# Grove_-_2_Channel_Inductive_Sensor_LDC16.net
KiCad netlist of a schematic drawn in EAGLE
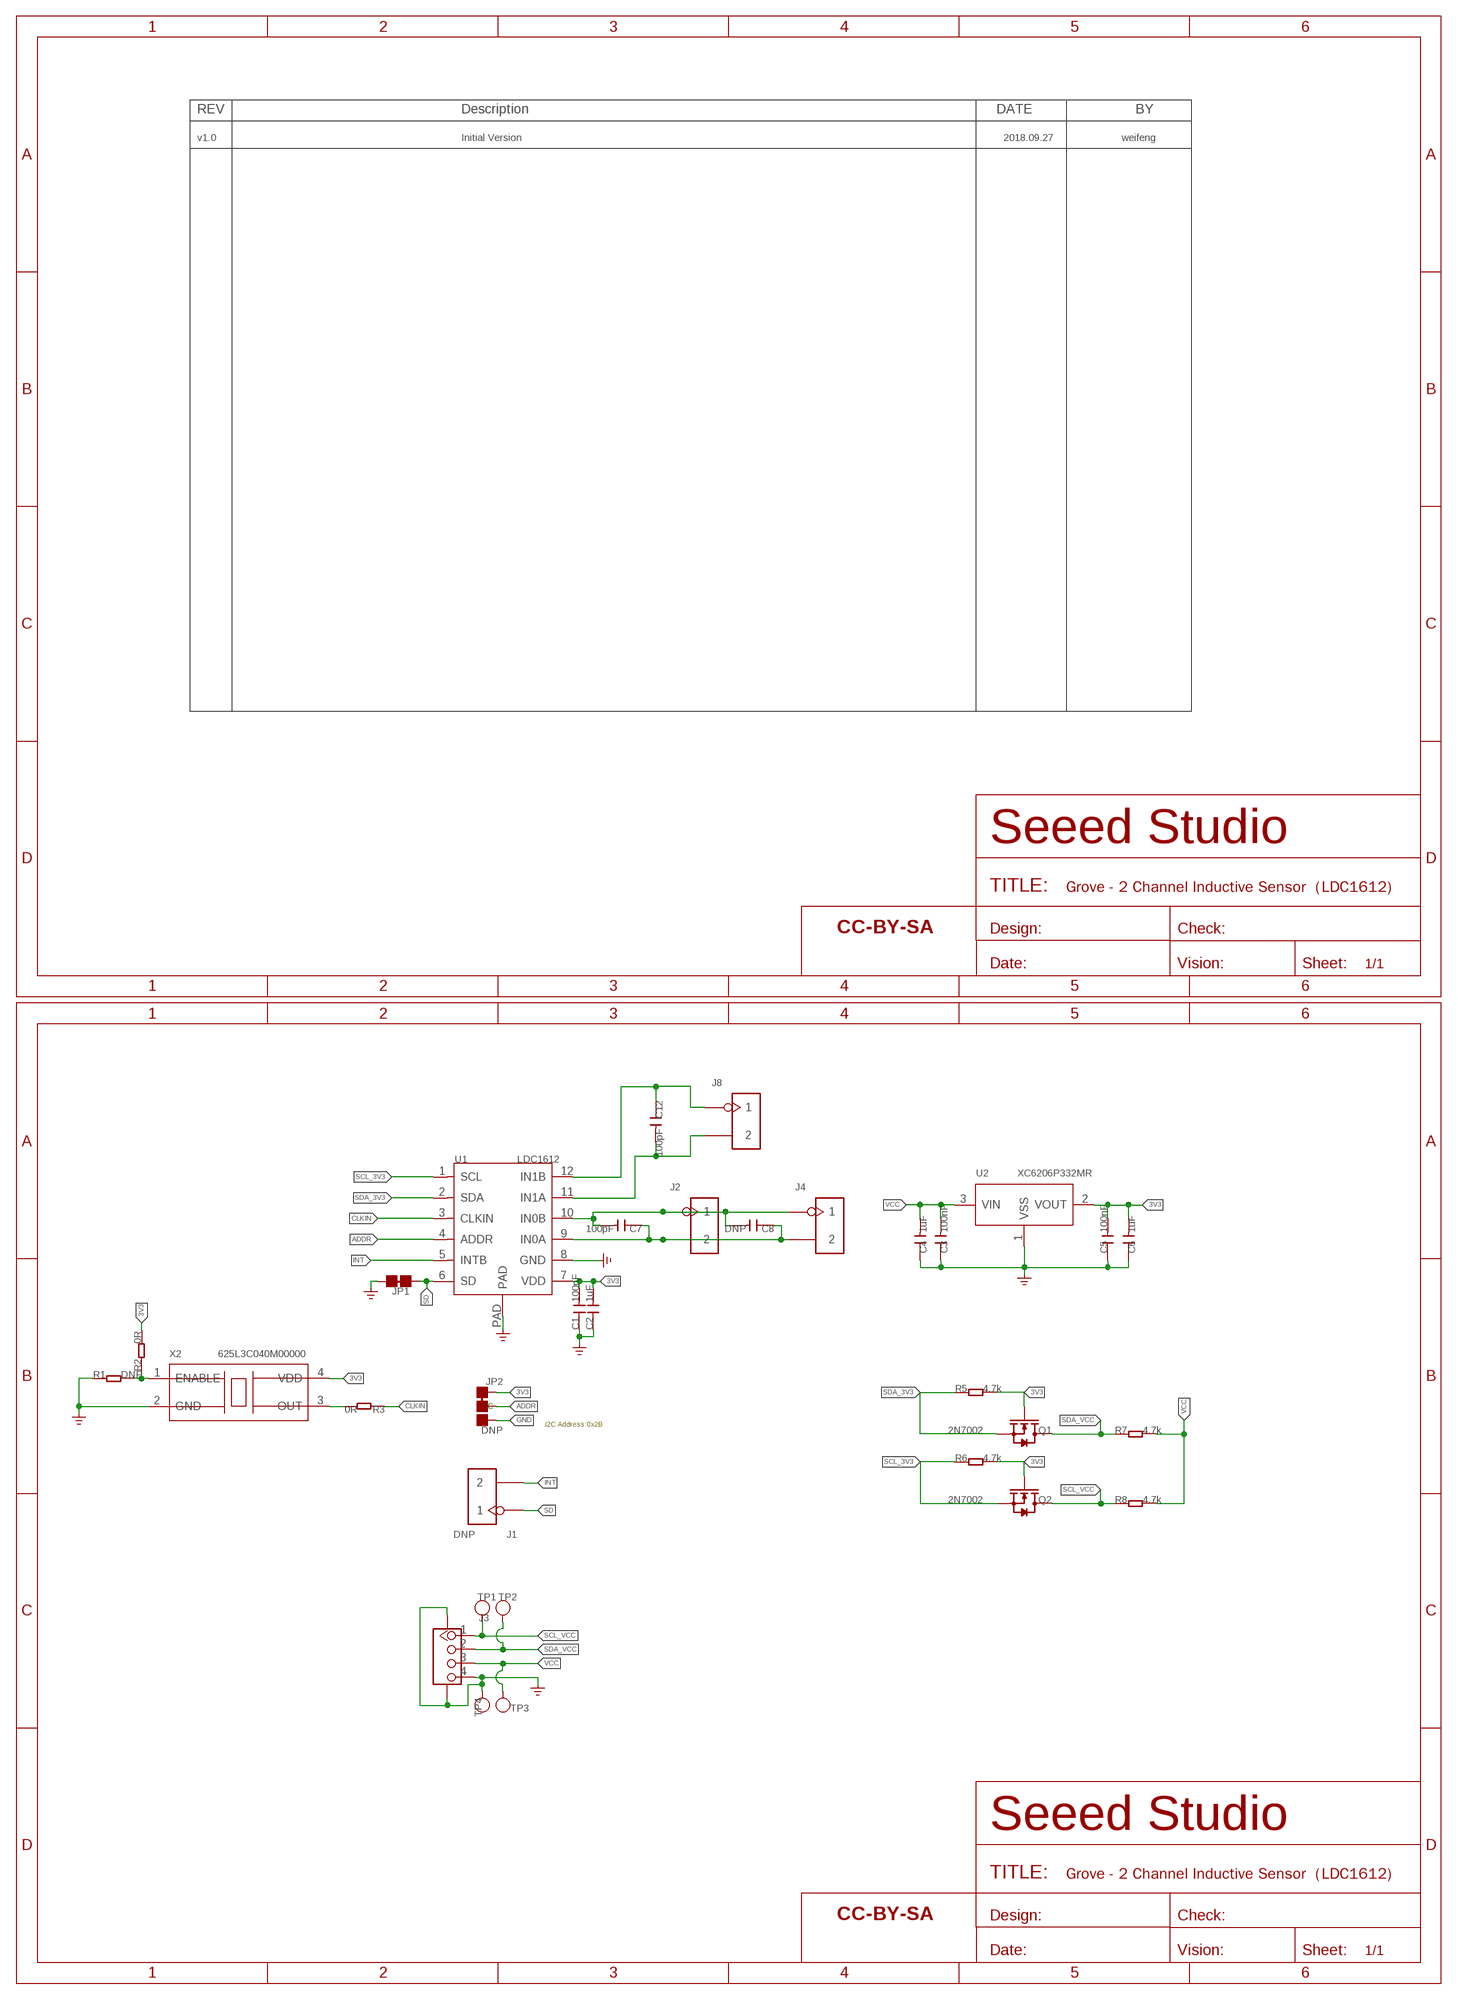
[diagram p0: schematic, sheet 1]

(export (version "E")
  (design (tool "Eeschema 10.0.6"))
  (components
    (comp (ref "C1")
      (value "100nF")
      (footprint "eagle-import:C0603")
      (libsource (lib "eagle-import") (part "CAP-0603"))
    )
    (comp (ref "C2")
      (value "1uF")
      (footprint "eagle-import:C0603")
      (libsource (lib "eagle-import") (part "CAP-0603"))
    )
    (comp (ref "C3")
      (value "100nF")
      (footprint "eagle-import:C0603")
      (libsource (lib "eagle-import") (part "CAP-0603"))
    )
    (comp (ref "C4")
      (value "1uF")
      (footprint "eagle-import:C0603")
      (libsource (lib "eagle-import") (part "CAP-0603"))
    )
    (comp (ref "C5")
      (value "100nF")
      (footprint "eagle-import:C0603")
      (libsource (lib "eagle-import") (part "CAP-0603"))
    )
    (comp (ref "C6")
      (value "1uF")
      (footprint "eagle-import:C0603")
      (libsource (lib "eagle-import") (part "CAP-0603"))
    )
    (comp (ref "C7")
      (value "100pF")
      (footprint "eagle-import:C0603")
      (libsource (lib "eagle-import") (part "CAP-0603"))
    )
    (comp (ref "C8")
      (value "DNP")
      (footprint "eagle-import:C0603")
      (libsource (lib "eagle-import") (part "CAP-0603"))
    )
    (comp (ref "C12")
      (value "100pF")
      (footprint "eagle-import:C0603")
      (libsource (lib "eagle-import") (part "CAP-0603"))
    )
    (comp (ref "FR1")
      (value "SEEEDSTUDIO-OPEN-SCH-FRAME")
      (footprint "eagle-import:SEEEDSTUDIO-PCB-FRAME")
      (libsource (lib "eagle-import") (part "SEEEDSTUDIO-OPEN-SCH-FRAME"))
    )
    (comp (ref "J1")
      (value "DNP")
      (footprint "eagle-import:H2-2.54")
      (libsource (lib "eagle-import") (part "HEADER-2P-65/35MIL"))
    )
    (comp (ref "J2")
      (value "HEADER-2P-65/35MIL")
      (footprint "eagle-import:H2-2.54")
      (libsource (lib "eagle-import") (part "HEADER-2P-65/35MIL"))
    )
    (comp (ref "J3")
      (value "GROVE-CONNECTOR-SMD'DD'")
      (footprint "eagle-import:HW4-SMD-2.0")
      (libsource (lib "eagle-import") (part "GROVE-CONNECTOR-SMD'DD'"))
    )
    (comp (ref "J4")
      (value "HEADER-2P-65/35MIL")
      (footprint "eagle-import:H2-2.54")
      (libsource (lib "eagle-import") (part "HEADER-2P-65/35MIL"))
    )
    (comp (ref "J8")
      (value "HEADER-2P-65/35MIL")
      (footprint "eagle-import:H2-2.54")
      (libsource (lib "eagle-import") (part "HEADER-2P-65/35MIL"))
    )
    (comp (ref "JP1")
      (value "JP-2P-SHORT")
      (footprint "eagle-import:2P-SMD-SHORT")
      (libsource (lib "eagle-import") (part "JP-2P-SHORT"))
    )
    (comp (ref "JP2")
      (value "DNP")
      (footprint "eagle-import:3P-SMD-SHORT")
      (libsource (lib "eagle-import") (part "JP-3P-SHORT"))
    )
    (comp (ref "Q1")
      (value "2N7002")
      (footprint "eagle-import:SOT-23")
      (libsource (lib "eagle-import") (part "MOSFET-N'SOT23'"))
    )
    (comp (ref "Q2")
      (value "2N7002")
      (footprint "eagle-import:SOT-23")
      (libsource (lib "eagle-import") (part "MOSFET-N'SOT23'"))
    )
    (comp (ref "R1")
      (value "DNP")
      (footprint "eagle-import:R0603")
      (libsource (lib "eagle-import") (part "RES-0603"))
    )
    (comp (ref "R2")
      (value "0R")
      (footprint "eagle-import:R0603")
      (libsource (lib "eagle-import") (part "RES-0603"))
    )
    (comp (ref "R3")
      (value "0R")
      (footprint "eagle-import:R0603")
      (libsource (lib "eagle-import") (part "RES-0603"))
    )
    (comp (ref "R5")
      (value "4.7k")
      (footprint "eagle-import:R0603")
      (libsource (lib "eagle-import") (part "RES-0603"))
    )
    (comp (ref "R6")
      (value "4.7k")
      (footprint "eagle-import:R0603")
      (libsource (lib "eagle-import") (part "RES-0603"))
    )
    (comp (ref "R7")
      (value "4.7k")
      (footprint "eagle-import:R0603")
      (libsource (lib "eagle-import") (part "RES-0603"))
    )
    (comp (ref "R8")
      (value "4.7k")
      (footprint "eagle-import:R0603")
      (libsource (lib "eagle-import") (part "RES-0603"))
    )
    (comp (ref "TP1")
      (value "TEST-POINT'4545'")
      (footprint "eagle-import:TP-D45MIL")
      (fields (field (name "PARTNO") "DNP"))
      (libsource (lib "eagle-import") (part "TEST-POINT'4545'"))
    )
    (comp (ref "TP2")
      (value "TEST-POINT'4545'")
      (footprint "eagle-import:TP-D45MIL")
      (fields (field (name "PARTNO") "DNP"))
      (libsource (lib "eagle-import") (part "TEST-POINT'4545'"))
    )
    (comp (ref "TP3")
      (value "TEST-POINT'4545'")
      (footprint "eagle-import:TP-D45MIL")
      (fields (field (name "PARTNO") "DNP"))
      (libsource (lib "eagle-import") (part "TEST-POINT'4545'"))
    )
    (comp (ref "TP4")
      (value "TEST-POINT'4545'")
      (footprint "eagle-import:TP-D45MIL")
      (fields (field (name "PARTNO") "DNP"))
      (libsource (lib "eagle-import") (part "TEST-POINT'4545'"))
    )
    (comp (ref "U$4")
      (value "SEEEDSTUDIO-OPEN-SCH-FRAME")
      (footprint "eagle-import:SEEEDSTUDIO-PCB-FRAME")
      (libsource (lib "eagle-import") (part "SEEEDSTUDIO-OPEN-SCH-FRAME"))
    )
    (comp (ref "U1")
      (value "LDC1612")
      (footprint "eagle-import:DFN12G-0.5-4X4MM")
      (libsource (lib "eagle-import") (part "DRIVER-LDC1612"))
    )
    (comp (ref "U2")
      (value "XC6206P332MR")
      (footprint "eagle-import:SOT-23")
      (libsource (lib "eagle-import") (part "PMIC-XC6206PMR"))
    )
    (comp (ref "X2")
      (value "625L3C040M00000")
      (footprint "eagle-import:OSC4-SMD-2.5X2.0X0.8MM")
      (libsource (lib "eagle-import") (part "CRYSTAL-OSCILLATOR-2.52.0"))
    )
  )
  (nets
    (net (code "1") (name "3V3") (class "Default")
      (node (ref "C1") (pin "2") (pinfunction "2_2") (pintype "passive"))
      (node (ref "C2") (pin "2") (pinfunction "2_2") (pintype "passive"))
      (node (ref "C5") (pin "2") (pinfunction "2_2") (pintype "passive"))
      (node (ref "C6") (pin "2") (pinfunction "2_2") (pintype "passive"))
      (node (ref "JP2") (pin "11") (pinfunction "L_11") (pintype "bidirectional"))
      (node (ref "Q1") (pin "1") (pinfunction "G_1") (pintype "passive"))
      (node (ref "Q2") (pin "1") (pinfunction "G_1") (pintype "passive"))
      (node (ref "R2") (pin "2") (pinfunction "2_2") (pintype "passive"))
      (node (ref "R5") (pin "2") (pinfunction "2_2") (pintype "passive"))
      (node (ref "R6") (pin "2") (pinfunction "2_2") (pintype "passive"))
      (node (ref "U1") (pin "7") (pinfunction "VDD_7") (pintype "bidirectional"))
      (node (ref "U2") (pin "2") (pinfunction "VOUT_2") (pintype "bidirectional"))
      (node (ref "X2") (pin "4") (pinfunction "VDD_4") (pintype "bidirectional"))
    )
    (net (code "2") (name "ADDR") (class "Default")
      (node (ref "JP2") (pin "MM") (pinfunction "C_MM") (pintype "bidirectional"))
      (node (ref "U1") (pin "4") (pinfunction "ADDR_4") (pintype "bidirectional"))
    )
    (net (code "3") (name "CLKIN") (class "Default")
      (node (ref "R3") (pin "1") (pinfunction "1_1") (pintype "passive"))
      (node (ref "U1") (pin "3") (pinfunction "CLKIN_3") (pintype "bidirectional"))
    )
    (net (code "4") (name "GND") (class "Default")
      (node (ref "C1") (pin "1") (pinfunction "1_1") (pintype "passive"))
      (node (ref "C2") (pin "1") (pinfunction "1_1") (pintype "passive"))
      (node (ref "C3") (pin "1") (pinfunction "1_1") (pintype "passive"))
      (node (ref "C4") (pin "1") (pinfunction "1_1") (pintype "passive"))
      (node (ref "C5") (pin "1") (pinfunction "1_1") (pintype "passive"))
      (node (ref "C6") (pin "1") (pinfunction "1_1") (pintype "passive"))
      (node (ref "J3") (pin "4") (pinfunction "4_4") (pintype "bidirectional"))
      (node (ref "J3") (pin "SS1") (pinfunction "SS1_SS1") (pintype "bidirectional"))
      (node (ref "J3") (pin "SS2") (pinfunction "SS2_SS2") (pintype "bidirectional"))
      (node (ref "JP1") (pin "1") (pinfunction "1_1") (pintype "bidirectional"))
      (node (ref "JP2") (pin "00") (pinfunction "R_00") (pintype "bidirectional"))
      (node (ref "R1") (pin "1") (pinfunction "1_1") (pintype "passive"))
      (node (ref "TP4") (pin "T") (pinfunction "T_T") (pintype "bidirectional"))
      (node (ref "U1") (pin "8") (pinfunction "GND_8") (pintype "bidirectional"))
      (node (ref "U1") (pin "PAD") (pinfunction "PAD_PAD") (pintype "bidirectional"))
      (node (ref "U2") (pin "1") (pinfunction "VSS_1") (pintype "bidirectional"))
      (node (ref "X2") (pin "2") (pinfunction "GND_2") (pintype "bidirectional"))
    )
    (net (code "5") (name "INT") (class "Default")
      (node (ref "J1") (pin "2") (pinfunction "2_2") (pintype "bidirectional"))
      (node (ref "U1") (pin "5") (pinfunction "INTB_5") (pintype "bidirectional"))
    )
    (net (code "6") (name "Net-(U1-IN0A)") (class "Default")
      (node (ref "C7") (pin "1") (pinfunction "1_1") (pintype "passive"))
      (node (ref "C8") (pin "1") (pinfunction "1_1") (pintype "passive"))
      (node (ref "J2") (pin "2") (pinfunction "2_2") (pintype "bidirectional"))
      (node (ref "J4") (pin "2") (pinfunction "2_2") (pintype "bidirectional"))
      (node (ref "U1") (pin "9") (pinfunction "IN0A_9") (pintype "bidirectional"))
    )
    (net (code "7") (name "Net-(U1-IN0B)") (class "Default")
      (node (ref "C7") (pin "2") (pinfunction "2_2") (pintype "passive"))
      (node (ref "C8") (pin "2") (pinfunction "2_2") (pintype "passive"))
      (node (ref "J2") (pin "1") (pinfunction "1_1") (pintype "bidirectional"))
      (node (ref "J4") (pin "1") (pinfunction "1_1") (pintype "bidirectional"))
      (node (ref "U1") (pin "10") (pinfunction "IN0B_10") (pintype "bidirectional"))
    )
    (net (code "8") (name "Net-(U1-IN1A)") (class "Default")
      (node (ref "C12") (pin "2") (pinfunction "2_2") (pintype "passive"))
      (node (ref "J8") (pin "2") (pinfunction "2_2") (pintype "bidirectional"))
      (node (ref "U1") (pin "11") (pinfunction "IN1A_11") (pintype "bidirectional"))
    )
    (net (code "9") (name "Net-(U1-IN1B)") (class "Default")
      (node (ref "C12") (pin "1") (pinfunction "1_1") (pintype "passive"))
      (node (ref "J8") (pin "1") (pinfunction "1_1") (pintype "bidirectional"))
      (node (ref "U1") (pin "12") (pinfunction "IN1B_12") (pintype "bidirectional"))
    )
    (net (code "10") (name "Net-(X2-ENABLE)") (class "Default")
      (node (ref "R1") (pin "2") (pinfunction "2_2") (pintype "passive"))
      (node (ref "R2") (pin "1") (pinfunction "1_1") (pintype "passive"))
      (node (ref "X2") (pin "1") (pinfunction "ENABLE_1") (pintype "bidirectional"))
    )
    (net (code "11") (name "Net-(X2-OUT)") (class "Default")
      (node (ref "R3") (pin "2") (pinfunction "2_2") (pintype "passive"))
      (node (ref "X2") (pin "3") (pinfunction "OUT_3") (pintype "bidirectional"))
    )
    (net (code "12") (name "SCL_3V3") (class "Default")
      (node (ref "Q2") (pin "2") (pinfunction "S_2") (pintype "passive"))
      (node (ref "R6") (pin "1") (pinfunction "1_1") (pintype "passive"))
      (node (ref "U1") (pin "1") (pinfunction "SCL_1") (pintype "bidirectional"))
    )
    (net (code "13") (name "SCL_VCC") (class "Default")
      (node (ref "J3") (pin "1") (pinfunction "1_1") (pintype "bidirectional"))
      (node (ref "Q2") (pin "3") (pinfunction "D_3") (pintype "passive"))
      (node (ref "R8") (pin "1") (pinfunction "1_1") (pintype "passive"))
      (node (ref "TP1") (pin "T") (pinfunction "T_T") (pintype "bidirectional"))
    )
    (net (code "14") (name "SD") (class "Default")
      (node (ref "J1") (pin "1") (pinfunction "1_1") (pintype "bidirectional"))
      (node (ref "JP1") (pin "2") (pinfunction "2_2") (pintype "bidirectional"))
      (node (ref "U1") (pin "6") (pinfunction "SD_6") (pintype "bidirectional"))
    )
    (net (code "15") (name "SDA_3V3") (class "Default")
      (node (ref "Q1") (pin "2") (pinfunction "S_2") (pintype "passive"))
      (node (ref "R5") (pin "1") (pinfunction "1_1") (pintype "passive"))
      (node (ref "U1") (pin "2") (pinfunction "SDA_2") (pintype "bidirectional"))
    )
    (net (code "16") (name "SDA_VCC") (class "Default")
      (node (ref "J3") (pin "2") (pinfunction "2_2") (pintype "bidirectional"))
      (node (ref "Q1") (pin "3") (pinfunction "D_3") (pintype "passive"))
      (node (ref "R7") (pin "1") (pinfunction "1_1") (pintype "passive"))
      (node (ref "TP2") (pin "T") (pinfunction "T_T") (pintype "bidirectional"))
    )
    (net (code "17") (name "VCC") (class "Default")
      (node (ref "C3") (pin "2") (pinfunction "2_2") (pintype "passive"))
      (node (ref "C4") (pin "2") (pinfunction "2_2") (pintype "passive"))
      (node (ref "J3") (pin "3") (pinfunction "3_3") (pintype "bidirectional"))
      (node (ref "R7") (pin "2") (pinfunction "2_2") (pintype "passive"))
      (node (ref "R8") (pin "2") (pinfunction "2_2") (pintype "passive"))
      (node (ref "TP3") (pin "T") (pinfunction "T_T") (pintype "bidirectional"))
      (node (ref "U2") (pin "3") (pinfunction "VIN_3") (pintype "bidirectional"))
    )
  )
)
